# fleischerTowR1.net
KiCad netlist of a schematic drawn in Altium Designer
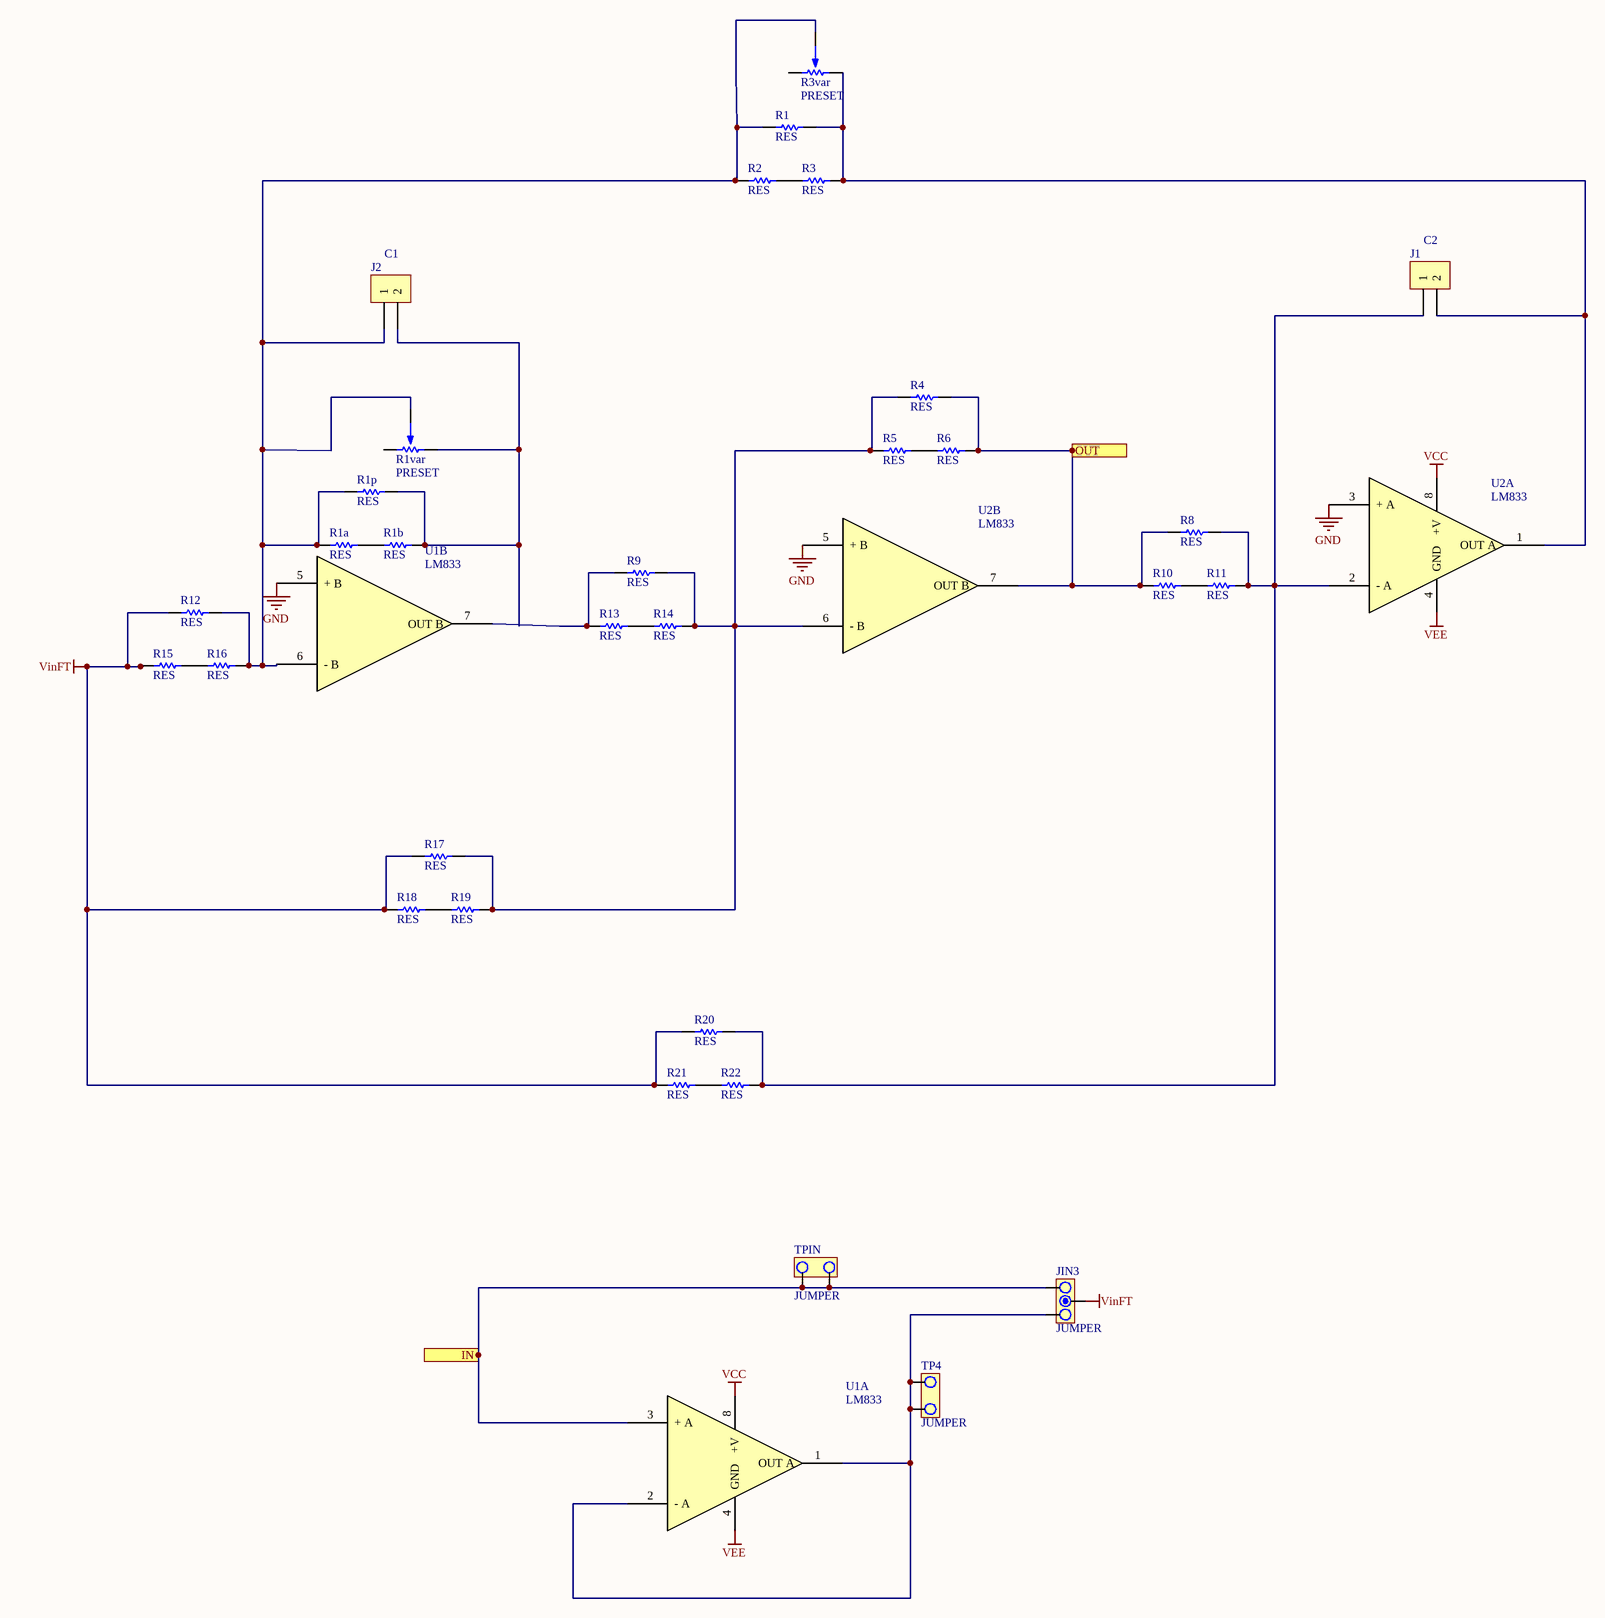
[diagram p0: fleischerTowR1.SchDoc]

(export (version "E")
  (design (tool "Eeschema 10.0.6"))
  (components
    (comp (ref "J1") (value "C2") (footprint "SIP2") (libsource (lib "LIBEBAL") (part "CON2")))
    (comp (ref "J2") (value "C1") (footprint "SIP2") (libsource (lib "LIBEBAL") (part "CON2")))
    (comp (ref "JIN3") (value "JUMPER") (footprint "JUMPER3") (libsource (lib "LIBEBAL") (part "JUMPER3")))
    (comp (ref "R1") (value "RES") (footprint "0805") (libsource (lib "LIBEBAL") (part "RES")))
    (comp (ref "R1a") (value "RES") (footprint "0805") (libsource (lib "LIBEBAL") (part "RES")))
    (comp (ref "R1b") (value "RES") (footprint "0805") (libsource (lib "LIBEBAL") (part "RES")))
    (comp (ref "R1p") (value "RES") (footprint "0805") (libsource (lib "LIBEBAL") (part "RES")))
    (comp (ref "R1var") (value "PRESET") (footprint "PRESET V") (libsource (lib "LIBEBAL") (part "PRESET")))
    (comp (ref "R2") (value "RES") (footprint "0805") (libsource (lib "LIBEBAL") (part "RES")))
    (comp (ref "R3") (value "RES") (footprint "0805") (libsource (lib "LIBEBAL") (part "RES")))
    (comp (ref "R3var") (value "PRESET") (footprint "PRESET V") (libsource (lib "LIBEBAL") (part "PRESET")))
    (comp (ref "R4") (value "RES") (footprint "0805") (libsource (lib "LIBEBAL") (part "RES")))
    (comp (ref "R5") (value "RES") (footprint "0805") (libsource (lib "LIBEBAL") (part "RES")))
    (comp (ref "R6") (value "RES") (footprint "0805") (libsource (lib "LIBEBAL") (part "RES")))
    (comp (ref "R8") (value "RES") (footprint "0805") (libsource (lib "LIBEBAL") (part "RES")))
    (comp (ref "R9") (value "RES") (footprint "0805") (libsource (lib "LIBEBAL") (part "RES")))
    (comp (ref "R10") (value "RES") (footprint "0805") (libsource (lib "LIBEBAL") (part "RES")))
    (comp (ref "R11") (value "RES") (footprint "0805") (libsource (lib "LIBEBAL") (part "RES")))
    (comp (ref "R12") (value "RES") (footprint "0805") (libsource (lib "LIBEBAL") (part "RES")))
    (comp (ref "R13") (value "RES") (footprint "0805") (libsource (lib "LIBEBAL") (part "RES")))
    (comp (ref "R14") (value "RES") (footprint "0805") (libsource (lib "LIBEBAL") (part "RES")))
    (comp (ref "R15") (value "RES") (footprint "0805") (libsource (lib "LIBEBAL") (part "RES")))
    (comp (ref "R16") (value "RES") (footprint "0805") (libsource (lib "LIBEBAL") (part "RES")))
    (comp (ref "R17") (value "RES") (footprint "0805") (libsource (lib "LIBEBAL") (part "RES")))
    (comp (ref "R18") (value "RES") (footprint "0805") (libsource (lib "LIBEBAL") (part "RES")))
    (comp (ref "R19") (value "RES") (footprint "0805") (libsource (lib "LIBEBAL") (part "RES")))
    (comp (ref "R20") (value "RES") (footprint "0805") (libsource (lib "LIBEBAL") (part "RES")))
    (comp (ref "R21") (value "RES") (footprint "0805") (libsource (lib "LIBEBAL") (part "RES")))
    (comp (ref "R22") (value "RES") (footprint "0805") (libsource (lib "LIBEBAL") (part "RES")))
    (comp (ref "TP4") (value "JUMPER") (footprint "JUMPER2") (libsource (lib "LIBEBAL") (part "JUMPER")))
    (comp (ref "TPIN") (value "JUMPER") (footprint "JUMPER2") (libsource (lib "") (part "JUMPER_1")))
    (comp (ref "U1")
      (value "LM833")
      (footprint "DIP8")
      (description "Dual Audio Operational Amplifier")
      (libsource (lib "LIBEBAL") (part "LM833"))
    )
    (comp (ref "U2")
      (value "LM833")
      (footprint "DIP8")
      (description "Dual Audio Operational Amplifier")
      (libsource (lib "LIBEBAL") (part "LM833"))
    )
  )
  (nets
    (net (code "1") (name "/IN") (class "Default")
      (node (ref "JIN3") (pin "3") (pinfunction "3_3") (pintype "passive"))
      (node (ref "TPIN") (pin "1") (pinfunction "1_1") (pintype "passive"))
      (node (ref "TPIN") (pin "2") (pinfunction "2_2") (pintype "passive"))
      (node (ref "U1") (pin "3") (pinfunction "+_A_3") (pintype "passive"))
    )
    (net (code "2") (name "/OUT") (class "Default")
      (node (ref "R10") (pin "1") (pinfunction "1_1") (pintype "passive"))
      (node (ref "R4") (pin "2") (pinfunction "2_2") (pintype "passive"))
      (node (ref "R6") (pin "2") (pinfunction "2_2") (pintype "passive"))
      (node (ref "R8") (pin "1") (pinfunction "1_1") (pintype "passive"))
      (node (ref "U2") (pin "7") (pinfunction "OUT_B_7") (pintype "passive"))
    )
    (net (code "3") (name "GND") (class "Default")
      (node (ref "U1") (pin "5") (pinfunction "+_B_5") (pintype "passive"))
      (node (ref "U2") (pin "3") (pinfunction "+_A_3") (pintype "passive"))
      (node (ref "U2") (pin "5") (pinfunction "+_B_5") (pintype "passive"))
    )
    (net (code "4") (name "Net-(J2-Pad2)") (class "Default")
      (node (ref "J2") (pin "2") (pinfunction "2_2") (pintype "passive"))
      (node (ref "R1b") (pin "2") (pinfunction "2_2") (pintype "passive"))
      (node (ref "R1p") (pin "2") (pinfunction "2_2") (pintype "passive"))
      (node (ref "R1var") (pin "3") (pinfunction "3_3") (pintype "passive"))
    )
    (net (code "5") (name "Net-(R1a-Pad2)") (class "Default")
      (node (ref "R1a") (pin "2") (pinfunction "2_2") (pintype "passive"))
      (node (ref "R1b") (pin "1") (pinfunction "1_1") (pintype "passive"))
    )
    (net (code "6") (name "Net-(R2-Pad2)") (class "Default")
      (node (ref "R2") (pin "2") (pinfunction "2_2") (pintype "passive"))
      (node (ref "R3") (pin "1") (pinfunction "1_1") (pintype "passive"))
    )
    (net (code "7") (name "Net-(R5-Pad2)") (class "Default")
      (node (ref "R5") (pin "2") (pinfunction "2_2") (pintype "passive"))
      (node (ref "R6") (pin "1") (pinfunction "1_1") (pintype "passive"))
    )
    (net (code "8") (name "Net-(R10-Pad2)") (class "Default")
      (node (ref "R10") (pin "2") (pinfunction "2_2") (pintype "passive"))
      (node (ref "R11") (pin "1") (pinfunction "1_1") (pintype "passive"))
    )
    (net (code "9") (name "Net-(R13-Pad2)") (class "Default")
      (node (ref "R13") (pin "2") (pinfunction "2_2") (pintype "passive"))
      (node (ref "R14") (pin "1") (pinfunction "1_1") (pintype "passive"))
    )
    (net (code "10") (name "Net-(R15-Pad2)") (class "Default")
      (node (ref "R15") (pin "2") (pinfunction "2_2") (pintype "passive"))
      (node (ref "R16") (pin "1") (pinfunction "1_1") (pintype "passive"))
    )
    (net (code "11") (name "Net-(R18-Pad2)") (class "Default")
      (node (ref "R18") (pin "2") (pinfunction "2_2") (pintype "passive"))
      (node (ref "R19") (pin "1") (pinfunction "1_1") (pintype "passive"))
    )
    (net (code "12") (name "Net-(R21-Pad2)") (class "Default")
      (node (ref "R21") (pin "2") (pinfunction "2_2") (pintype "passive"))
      (node (ref "R22") (pin "1") (pinfunction "1_1") (pintype "passive"))
    )
    (net (code "13") (name "Net-(U1A--_A)") (class "Default")
      (node (ref "JIN3") (pin "1") (pinfunction "1_1") (pintype "passive"))
      (node (ref "TP4") (pin "1") (pinfunction "1_1") (pintype "passive"))
      (node (ref "TP4") (pin "2") (pinfunction "2_2") (pintype "passive"))
      (node (ref "U1") (pin "1") (pinfunction "OUT_A_1") (pintype "passive"))
      (node (ref "U1") (pin "2") (pinfunction "-_A_2") (pintype "passive"))
    )
    (net (code "14") (name "Net-(U1B--_B)") (class "Default")
      (node (ref "J2") (pin "1") (pinfunction "1_1") (pintype "passive"))
      (node (ref "R1") (pin "1") (pinfunction "1_1") (pintype "passive"))
      (node (ref "R12") (pin "2") (pinfunction "2_2") (pintype "passive"))
      (node (ref "R16") (pin "2") (pinfunction "2_2") (pintype "passive"))
      (node (ref "R1a") (pin "1") (pinfunction "1_1") (pintype "passive"))
      (node (ref "R1p") (pin "1") (pinfunction "1_1") (pintype "passive"))
      (node (ref "R1var") (pin "2") (pinfunction "2_2") (pintype "passive"))
      (node (ref "R2") (pin "1") (pinfunction "1_1") (pintype "passive"))
      (node (ref "R3var") (pin "2") (pinfunction "2_2") (pintype "passive"))
      (node (ref "U1") (pin "6") (pinfunction "-_B_6") (pintype "passive"))
    )
    (net (code "15") (name "Net-(U1B-OUT_B)") (class "Default")
      (node (ref "R13") (pin "1") (pinfunction "1_1") (pintype "passive"))
      (node (ref "R9") (pin "1") (pinfunction "1_1") (pintype "passive"))
      (node (ref "U1") (pin "7") (pinfunction "OUT_B_7") (pintype "passive"))
    )
    (net (code "16") (name "Net-(U2A--_A)") (class "Default")
      (node (ref "J1") (pin "1") (pinfunction "1_1") (pintype "passive"))
      (node (ref "R11") (pin "2") (pinfunction "2_2") (pintype "passive"))
      (node (ref "R20") (pin "2") (pinfunction "2_2") (pintype "passive"))
      (node (ref "R22") (pin "2") (pinfunction "2_2") (pintype "passive"))
      (node (ref "R8") (pin "2") (pinfunction "2_2") (pintype "passive"))
      (node (ref "U2") (pin "2") (pinfunction "-_A_2") (pintype "passive"))
    )
    (net (code "17") (name "Net-(U2A-OUT_A)") (class "Default")
      (node (ref "J1") (pin "2") (pinfunction "2_2") (pintype "passive"))
      (node (ref "R1") (pin "2") (pinfunction "2_2") (pintype "passive"))
      (node (ref "R3") (pin "2") (pinfunction "2_2") (pintype "passive"))
      (node (ref "R3var") (pin "3") (pinfunction "3_3") (pintype "passive"))
      (node (ref "U2") (pin "1") (pinfunction "OUT_A_1") (pintype "passive"))
    )
    (net (code "18") (name "Net-(U2B--_B)") (class "Default")
      (node (ref "R14") (pin "2") (pinfunction "2_2") (pintype "passive"))
      (node (ref "R17") (pin "2") (pinfunction "2_2") (pintype "passive"))
      (node (ref "R19") (pin "2") (pinfunction "2_2") (pintype "passive"))
      (node (ref "R4") (pin "1") (pinfunction "1_1") (pintype "passive"))
      (node (ref "R5") (pin "1") (pinfunction "1_1") (pintype "passive"))
      (node (ref "R9") (pin "2") (pinfunction "2_2") (pintype "passive"))
      (node (ref "U2") (pin "6") (pinfunction "-_B_6") (pintype "passive"))
    )
    (net (code "19") (name "VCC") (class "Default")
      (node (ref "U1") (pin "8") (pinfunction "+V_8") (pintype "passive"))
      (node (ref "U2") (pin "8") (pinfunction "+V_8") (pintype "passive"))
    )
    (net (code "20") (name "VEE") (class "Default")
      (node (ref "U1") (pin "4") (pinfunction "GND_4") (pintype "passive"))
      (node (ref "U2") (pin "4") (pinfunction "GND_4") (pintype "passive"))
    )
    (net (code "21") (name "VinFT") (class "Default")
      (node (ref "JIN3") (pin "2") (pinfunction "2_2") (pintype "passive"))
      (node (ref "R12") (pin "1") (pinfunction "1_1") (pintype "passive"))
      (node (ref "R15") (pin "1") (pinfunction "1_1") (pintype "passive"))
      (node (ref "R17") (pin "1") (pinfunction "1_1") (pintype "passive"))
      (node (ref "R18") (pin "1") (pinfunction "1_1") (pintype "passive"))
      (node (ref "R20") (pin "1") (pinfunction "1_1") (pintype "passive"))
      (node (ref "R21") (pin "1") (pinfunction "1_1") (pintype "passive"))
    )
    (net (code "22") (name "unconnected-(R1var-Pad1)") (class "Default")
      (node (ref "R1var") (pin "1") (pinfunction "1_1") (pintype "passive"))
    )
    (net (code "23") (name "unconnected-(R3var-Pad1)") (class "Default")
      (node (ref "R3var") (pin "1") (pinfunction "1_1") (pintype "passive"))
    )
  )
)
